# USBasp.net
KiCad netlist of a schematic drawn in EAGLE
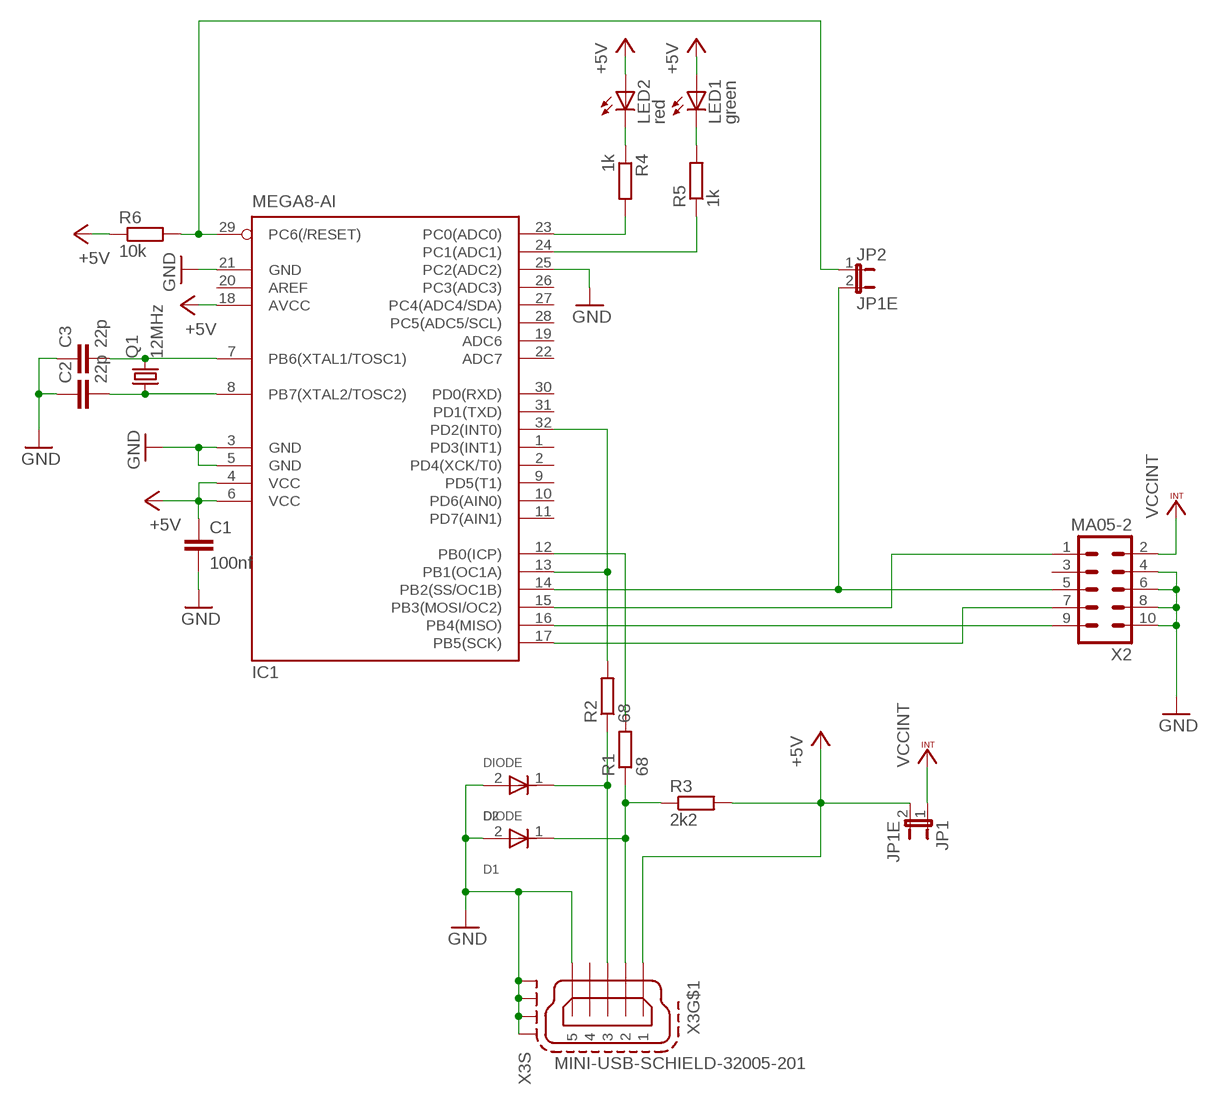
[diagram p0: schematic, sheet 1]

(export (version "E")
  (design (tool "Eeschema 10.0.6"))
  (components
    (comp (ref "C1")
      (value "100nf")
      (footprint "eagle-import:C0805")
      (libsource (lib "eagle-import") (part "C-EUC0805"))
    )
    (comp (ref "C2")
      (value "22p")
      (footprint "eagle-import:C0805")
      (libsource (lib "eagle-import") (part "C-EUC0805"))
    )
    (comp (ref "C3")
      (value "22p")
      (footprint "eagle-import:C0805")
      (libsource (lib "eagle-import") (part "C-EUC0805"))
    )
    (comp (ref "D1")
      (value "DIODE")
      (footprint "eagle-import:SOD80")
      (libsource (lib "eagle-import") (part "DIODE"))
    )
    (comp (ref "D2")
      (value "DIODE")
      (footprint "eagle-import:SOD80")
      (libsource (lib "eagle-import") (part "DIODE"))
    )
    (comp (ref "IC1")
      (value "MEGA8-AI")
      (footprint "eagle-import:TQFP32-08")
      (fields (field (name "MPN") "ATMEGA8-16AU"))
      (libsource (lib "eagle-import") (part "MEGA8-AI"))
    )
    (comp (ref "JP1")
      (value "JP1E")
      (footprint "eagle-import:JP0603")
      (libsource (lib "eagle-import") (part "JP1E"))
    )
    (comp (ref "JP2")
      (value "JP1E")
      (footprint "eagle-import:JP0603")
      (libsource (lib "eagle-import") (part "JP1E"))
    )
    (comp (ref "LED1")
      (value "green")
      (footprint "eagle-import:CHIPLED_0603")
      (libsource (lib "eagle-import") (part "LEDCHIPLED_0603"))
    )
    (comp (ref "LED2")
      (value "red")
      (footprint "eagle-import:CHIPLED_0603")
      (libsource (lib "eagle-import") (part "LEDCHIPLED_0603"))
    )
    (comp (ref "Q1")
      (value "12MHz")
      (footprint "eagle-import:HC49_S")
      (libsource (lib "eagle-import") (part "CRYSTALHC49S"))
    )
    (comp (ref "R1")
      (value "68")
      (footprint "eagle-import:R0603")
      (libsource (lib "eagle-import") (part "R-EU_R0603"))
    )
    (comp (ref "R2")
      (value "68")
      (footprint "eagle-import:R0603")
      (libsource (lib "eagle-import") (part "R-EU_R0603"))
    )
    (comp (ref "R3")
      (value "2k2")
      (footprint "eagle-import:R0603")
      (libsource (lib "eagle-import") (part "R-EU_R0603"))
    )
    (comp (ref "R4")
      (value "1k")
      (footprint "eagle-import:R0603")
      (libsource (lib "eagle-import") (part "R-EU_R0603"))
    )
    (comp (ref "R5")
      (value "1k")
      (footprint "eagle-import:R0603")
      (libsource (lib "eagle-import") (part "R-EU_R0603"))
    )
    (comp (ref "R6")
      (value "10k")
      (footprint "eagle-import:R0603")
      (libsource (lib "eagle-import") (part "R-EU_R0603"))
    )
    (comp (ref "X2")
      (value "MA05-2")
      (footprint "eagle-import:MA05-2")
      (libsource (lib "eagle-import") (part "MA05-2"))
    )
    (comp (ref "X3")
      (value "MINI-USB-SCHIELD-32005-201")
      (footprint "eagle-import:32005-201")
      (libsource (lib "eagle-import") (part "MINI-USB-SCHIELD-32005-201"))
    )
  )
  (nets
    (net (code "1") (name "+5V") (class "Default")
      (node (ref "C1") (pin "1") (pinfunction "1_1") (pintype "passive"))
      (node (ref "IC1") (pin "18") (pinfunction "AVCC_18") (pintype "power_in"))
      (node (ref "IC1") (pin "4") (pinfunction "VCC_4") (pintype "power_in"))
      (node (ref "IC1") (pin "6") (pinfunction "VCC_6") (pintype "power_in"))
      (node (ref "JP1") (pin "2") (pinfunction "2_2") (pintype "passive"))
      (node (ref "LED1") (pin "A") (pinfunction "A_A") (pintype "passive"))
      (node (ref "LED2") (pin "A") (pinfunction "A_A") (pintype "passive"))
      (node (ref "R3") (pin "2") (pinfunction "2_2") (pintype "passive"))
      (node (ref "R6") (pin "1") (pinfunction "1_1") (pintype "passive"))
      (node (ref "X3") (pin "1") (pinfunction "1_1") (pintype "passive"))
    )
    (net (code "2") (name "GND") (class "Default")
      (node (ref "C1") (pin "2") (pinfunction "2_2") (pintype "passive"))
      (node (ref "C2") (pin "1") (pinfunction "1_1") (pintype "passive"))
      (node (ref "C3") (pin "1") (pinfunction "1_1") (pintype "passive"))
      (node (ref "D1") (pin "2") (pinfunction "ANOD_2") (pintype "power_in"))
      (node (ref "D2") (pin "2") (pinfunction "ANOD_2") (pintype "power_in"))
      (node (ref "IC1") (pin "21") (pinfunction "GND_21") (pintype "power_in"))
      (node (ref "IC1") (pin "25") (pinfunction "PC2(ADC2)_25") (pintype "bidirectional"))
      (node (ref "IC1") (pin "3") (pinfunction "GND_3") (pintype "power_in"))
      (node (ref "IC1") (pin "5") (pinfunction "GND_5") (pintype "power_in"))
      (node (ref "X2") (pin "10") (pinfunction "10_10") (pintype "passive"))
      (node (ref "X2") (pin "4") (pinfunction "4_4") (pintype "passive"))
      (node (ref "X2") (pin "6") (pinfunction "6_6") (pintype "passive"))
      (node (ref "X2") (pin "8") (pinfunction "8_8") (pintype "passive"))
      (node (ref "X3") (pin "5") (pinfunction "5_5") (pintype "passive"))
      (node (ref "X3") (pin "M1") (pinfunction "S1_M1") (pintype "passive"))
      (node (ref "X3") (pin "M2") (pinfunction "S2_M2") (pintype "passive"))
      (node (ref "X3") (pin "M3") (pinfunction "S3_M3") (pintype "passive"))
      (node (ref "X3") (pin "M4") (pinfunction "S4_M4") (pintype "passive"))
    )
    (net (code "3") (name "Net-(D1-KATOD)") (class "Default")
      (node (ref "D1") (pin "1") (pinfunction "KATOD_1") (pintype "power_in"))
      (node (ref "R1") (pin "1") (pinfunction "1_1") (pintype "passive"))
      (node (ref "R3") (pin "1") (pinfunction "1_1") (pintype "passive"))
      (node (ref "X3") (pin "2") (pinfunction "2_2") (pintype "passive"))
    )
    (net (code "4") (name "Net-(D2-KATOD)") (class "Default")
      (node (ref "D2") (pin "1") (pinfunction "KATOD_1") (pintype "power_in"))
      (node (ref "R2") (pin "1") (pinfunction "1_1") (pintype "passive"))
      (node (ref "X3") (pin "3") (pinfunction "3_3") (pintype "passive"))
    )
    (net (code "5") (name "Net-(IC1-PB0(ICP))") (class "Default")
      (node (ref "IC1") (pin "12") (pinfunction "PB0(ICP)_12") (pintype "bidirectional"))
      (node (ref "R1") (pin "2") (pinfunction "2_2") (pintype "passive"))
    )
    (net (code "6") (name "Net-(IC1-PB1(OC1A))") (class "Default")
      (node (ref "IC1") (pin "13") (pinfunction "PB1(OC1A)_13") (pintype "bidirectional"))
      (node (ref "IC1") (pin "32") (pinfunction "PD2(INT0)_32") (pintype "bidirectional"))
      (node (ref "R2") (pin "2") (pinfunction "2_2") (pintype "passive"))
    )
    (net (code "7") (name "Net-(IC1-PB2(SS{slash}OC1B))") (class "Default")
      (node (ref "IC1") (pin "14") (pinfunction "PB2(SS/OC1B)_14") (pintype "bidirectional"))
      (node (ref "JP2") (pin "2") (pinfunction "2_2") (pintype "passive"))
      (node (ref "X2") (pin "5") (pinfunction "5_5") (pintype "passive"))
    )
    (net (code "8") (name "Net-(IC1-PB3(MOSI{slash}OC2))") (class "Default")
      (node (ref "IC1") (pin "15") (pinfunction "PB3(MOSI/OC2)_15") (pintype "bidirectional"))
      (node (ref "X2") (pin "1") (pinfunction "1_1") (pintype "passive"))
    )
    (net (code "9") (name "Net-(IC1-PB4(MISO))") (class "Default")
      (node (ref "IC1") (pin "16") (pinfunction "PB4(MISO)_16") (pintype "bidirectional"))
      (node (ref "X2") (pin "9") (pinfunction "9_9") (pintype "passive"))
    )
    (net (code "10") (name "Net-(IC1-PB5(SCK))") (class "Default")
      (node (ref "IC1") (pin "17") (pinfunction "PB5(SCK)_17") (pintype "bidirectional"))
      (node (ref "X2") (pin "7") (pinfunction "7_7") (pintype "passive"))
    )
    (net (code "11") (name "Net-(IC1-PB6(XTAL1{slash}TOSC1))") (class "Default")
      (node (ref "C3") (pin "2") (pinfunction "2_2") (pintype "passive"))
      (node (ref "IC1") (pin "7") (pinfunction "PB6(XTAL1/TOSC1)_7") (pintype "bidirectional"))
      (node (ref "Q1") (pin "2") (pinfunction "2_2") (pintype "passive"))
    )
    (net (code "12") (name "Net-(IC1-PB7(XTAL2{slash}TOSC2))") (class "Default")
      (node (ref "C2") (pin "2") (pinfunction "2_2") (pintype "passive"))
      (node (ref "IC1") (pin "8") (pinfunction "PB7(XTAL2/TOSC2)_8") (pintype "bidirectional"))
      (node (ref "Q1") (pin "1") (pinfunction "1_1") (pintype "passive"))
    )
    (net (code "13") (name "Net-(IC1-PC0(ADC0))") (class "Default")
      (node (ref "IC1") (pin "23") (pinfunction "PC0(ADC0)_23") (pintype "bidirectional"))
      (node (ref "R4") (pin "2") (pinfunction "2_2") (pintype "passive"))
    )
    (net (code "14") (name "Net-(IC1-PC1(ADC1))") (class "Default")
      (node (ref "IC1") (pin "24") (pinfunction "PC1(ADC1)_24") (pintype "bidirectional"))
      (node (ref "R5") (pin "1") (pinfunction "1_1") (pintype "passive"))
    )
    (net (code "15") (name "Net-(IC1-PC6({slash}RESET))") (class "Default")
      (node (ref "IC1") (pin "29") (pinfunction "PC6(/RESET)_29") (pintype "bidirectional"))
      (node (ref "JP2") (pin "1") (pinfunction "1_1") (pintype "passive"))
      (node (ref "R6") (pin "2") (pinfunction "2_2") (pintype "passive"))
    )
    (net (code "16") (name "Net-(LED1-PadC)") (class "Default")
      (node (ref "LED1") (pin "C") (pinfunction "C_C") (pintype "passive"))
      (node (ref "R5") (pin "2") (pinfunction "2_2") (pintype "passive"))
    )
    (net (code "17") (name "Net-(LED2-PadC)") (class "Default")
      (node (ref "LED2") (pin "C") (pinfunction "C_C") (pintype "passive"))
      (node (ref "R4") (pin "1") (pinfunction "1_1") (pintype "passive"))
    )
    (net (code "18") (name "VCCINT") (class "Default")
      (node (ref "JP1") (pin "1") (pinfunction "1_1") (pintype "passive"))
      (node (ref "X2") (pin "2") (pinfunction "2_2") (pintype "passive"))
    )
    (net (code "19") (name "unconnected-(IC1-ADC6-Pad19)") (class "Default")
      (node (ref "IC1") (pin "19") (pinfunction "ADC6_19") (pintype "bidirectional"))
    )
    (net (code "20") (name "unconnected-(IC1-ADC7-Pad22)") (class "Default")
      (node (ref "IC1") (pin "22") (pinfunction "ADC7_22") (pintype "bidirectional"))
    )
    (net (code "21") (name "unconnected-(IC1-AREF-Pad20)") (class "Default")
      (node (ref "IC1") (pin "20") (pinfunction "AREF_20") (pintype "passive"))
    )
    (net (code "22") (name "unconnected-(IC1-PC3(ADC3)-Pad26)") (class "Default")
      (node (ref "IC1") (pin "26") (pinfunction "PC3(ADC3)_26") (pintype "bidirectional"))
    )
    (net (code "23") (name "unconnected-(IC1-PC4(ADC4{slash}SDA)-Pad27)") (class "Default")
      (node (ref "IC1") (pin "27") (pinfunction "PC4(ADC4/SDA)_27") (pintype "bidirectional"))
    )
    (net (code "24") (name "unconnected-(IC1-PC5(ADC5{slash}SCL)-Pad28)") (class "Default")
      (node (ref "IC1") (pin "28") (pinfunction "PC5(ADC5/SCL)_28") (pintype "bidirectional"))
    )
    (net (code "25") (name "unconnected-(IC1-PD0(RXD)-Pad30)") (class "Default")
      (node (ref "IC1") (pin "30") (pinfunction "PD0(RXD)_30") (pintype "bidirectional"))
    )
    (net (code "26") (name "unconnected-(IC1-PD1(TXD)-Pad31)") (class "Default")
      (node (ref "IC1") (pin "31") (pinfunction "PD1(TXD)_31") (pintype "bidirectional"))
    )
    (net (code "27") (name "unconnected-(IC1-PD3(INT1)-Pad1)") (class "Default")
      (node (ref "IC1") (pin "1") (pinfunction "PD3(INT1)_1") (pintype "bidirectional"))
    )
    (net (code "28") (name "unconnected-(IC1-PD4(XCK{slash}T0)-Pad2)") (class "Default")
      (node (ref "IC1") (pin "2") (pinfunction "PD4(XCK/T0)_2") (pintype "bidirectional"))
    )
    (net (code "29") (name "unconnected-(IC1-PD5(T1)-Pad9)") (class "Default")
      (node (ref "IC1") (pin "9") (pinfunction "PD5(T1)_9") (pintype "bidirectional"))
    )
    (net (code "30") (name "unconnected-(IC1-PD6(AIN0)-Pad10)") (class "Default")
      (node (ref "IC1") (pin "10") (pinfunction "PD6(AIN0)_10") (pintype "bidirectional"))
    )
    (net (code "31") (name "unconnected-(IC1-PD7(AIN1)-Pad11)") (class "Default")
      (node (ref "IC1") (pin "11") (pinfunction "PD7(AIN1)_11") (pintype "bidirectional"))
    )
    (net (code "32") (name "unconnected-(X2-Pad3)") (class "Default")
      (node (ref "X2") (pin "3") (pinfunction "3_3") (pintype "passive"))
    )
    (net (code "33") (name "unconnected-(X3-Pad4)") (class "Default")
      (node (ref "X3") (pin "4") (pinfunction "4_4") (pintype "passive"))
    )
  )
)
